# DigiDendro.net
KiCad netlist of a schematic drawn in EAGLE
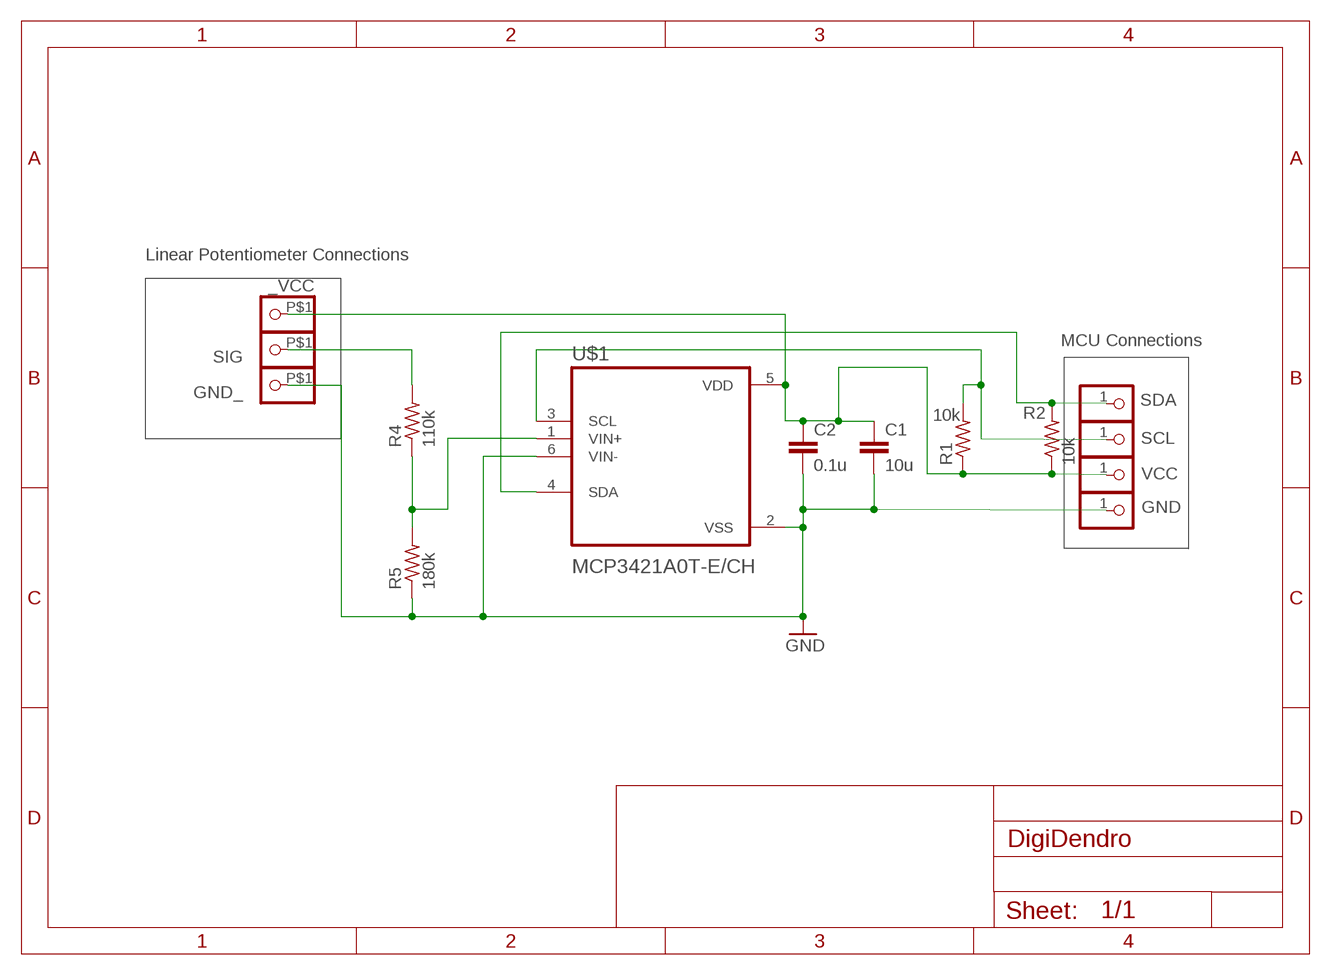
[diagram p0: schematic, sheet 1]

(export (version "E")
  (design (tool "Eeschema 10.0.6"))
  (components
    (comp (ref "C1")
      (value "10u")
      (footprint "eagle-import:C0805")
      (libsource (lib "eagle-import") (part "C-EUC0805"))
    )
    (comp (ref "C2")
      (value "0.1u")
      (footprint "eagle-import:C0805")
      (libsource (lib "eagle-import") (part "C-EUC0805"))
    )
    (comp (ref "GND")
      (value "PINHD-1X1")
      (footprint "eagle-import:1X01")
      (libsource (lib "eagle-import") (part "pinhead_325_PINHD-1X1"))
    )
    (comp (ref "GND_")
      (value "PINHD-1X1-BIGPOGO")
      (footprint "eagle-import:1X1-BIGPOGO")
      (libsource (lib "eagle-import") (part "PINHD-1X1-BIGPOGO"))
    )
    (comp (ref "R1")
      (value "10k")
      (footprint "eagle-import:R0603")
      (libsource (lib "eagle-import") (part "R-US_R0603"))
    )
    (comp (ref "R2")
      (value "10k")
      (footprint "eagle-import:R0603")
      (libsource (lib "eagle-import") (part "R-US_R0603"))
    )
    (comp (ref "R4")
      (value "110k")
      (footprint "eagle-import:R0603")
      (libsource (lib "eagle-import") (part "R-US_R0603"))
    )
    (comp (ref "R5")
      (value "180k")
      (footprint "eagle-import:R0603")
      (libsource (lib "eagle-import") (part "R-US_R0603"))
    )
    (comp (ref "SCL")
      (value "PINHD-1X1")
      (footprint "eagle-import:1X01")
      (libsource (lib "eagle-import") (part "pinhead_325_PINHD-1X1"))
    )
    (comp (ref "SDA")
      (value "PINHD-1X1")
      (footprint "eagle-import:1X01")
      (fields (field (name "SPICEPREFIX") "X"))
      (libsource (lib "eagle-import") (part "pinhead_325_PINHD-1X1"))
    )
    (comp (ref "SIG")
      (value "PINHD-1X1-BIGPOGO")
      (footprint "eagle-import:1X1-BIGPOGO")
      (libsource (lib "eagle-import") (part "PINHD-1X1-BIGPOGO"))
    )
    (comp (ref "U$1")
      (value "MCP3421A0T-E/CH")
      (footprint "eagle-import:SOT95P280X145-6N")
      (fields (field (name "MF") "Microchip"))
      (libsource (lib "eagle-import") (part "MCP3421A0T-E/CH"))
    )
    (comp (ref "VCC")
      (value "PINHD-1X1")
      (footprint "eagle-import:1X01")
      (libsource (lib "eagle-import") (part "pinhead_325_PINHD-1X1"))
    )
    (comp (ref "_VCC")
      (value "PINHD-1X1-BIGPOGO")
      (footprint "eagle-import:1X1-BIGPOGO")
      (libsource (lib "eagle-import") (part "PINHD-1X1-BIGPOGO"))
    )
  )
  (nets
    (net (code "1") (name "GND") (class "Default")
      (node (ref "C1") (pin "2") (pinfunction "2_2") (pintype "passive"))
      (node (ref "C2") (pin "2") (pinfunction "2_2") (pintype "passive"))
      (node (ref "GND") (pin "1") (pinfunction "1_1") (pintype "passive"))
      (node (ref "GND_") (pin "P$1") (pinfunction "1_P$1") (pintype "passive"))
      (node (ref "R5") (pin "1") (pinfunction "1_1") (pintype "passive"))
      (node (ref "U$1") (pin "2") (pinfunction "VSS_2") (pintype "power_in"))
      (node (ref "U$1") (pin "6") (pinfunction "VIN-_6") (pintype "input"))
    )
    (net (code "2") (name "Net-(SIG-1)") (class "Default")
      (node (ref "R4") (pin "2") (pinfunction "2_2") (pintype "passive"))
      (node (ref "SIG") (pin "P$1") (pinfunction "1_P$1") (pintype "passive"))
    )
    (net (code "3") (name "Net-(U$1-SCL)") (class "Default")
      (node (ref "R1") (pin "2") (pinfunction "2_2") (pintype "passive"))
      (node (ref "SCL") (pin "1") (pinfunction "1_1") (pintype "passive"))
      (node (ref "U$1") (pin "3") (pinfunction "SCL_3") (pintype "input"))
    )
    (net (code "4") (name "Net-(U$1-SDA)") (class "Default")
      (node (ref "R2") (pin "2") (pinfunction "2_2") (pintype "passive"))
      (node (ref "SDA") (pin "1") (pinfunction "1_1") (pintype "passive"))
      (node (ref "U$1") (pin "4") (pinfunction "SDA_4") (pintype "bidirectional"))
    )
    (net (code "5") (name "Net-(U$1-VDD)") (class "Default")
      (node (ref "C1") (pin "1") (pinfunction "1_1") (pintype "passive"))
      (node (ref "C2") (pin "1") (pinfunction "1_1") (pintype "passive"))
      (node (ref "R1") (pin "1") (pinfunction "1_1") (pintype "passive"))
      (node (ref "R2") (pin "1") (pinfunction "1_1") (pintype "passive"))
      (node (ref "U$1") (pin "5") (pinfunction "VDD_5") (pintype "power_in"))
      (node (ref "VCC") (pin "1") (pinfunction "1_1") (pintype "passive"))
      (node (ref "_VCC") (pin "P$1") (pinfunction "1_P$1") (pintype "passive"))
    )
    (net (code "6") (name "Net-(U$1-VIN+)") (class "Default")
      (node (ref "R4") (pin "1") (pinfunction "1_1") (pintype "passive"))
      (node (ref "R5") (pin "2") (pinfunction "2_2") (pintype "passive"))
      (node (ref "U$1") (pin "1") (pinfunction "VIN+_1") (pintype "input"))
    )
  )
)
